# alterable.net
KiCad netlist of a schematic drawn in Altium Designer
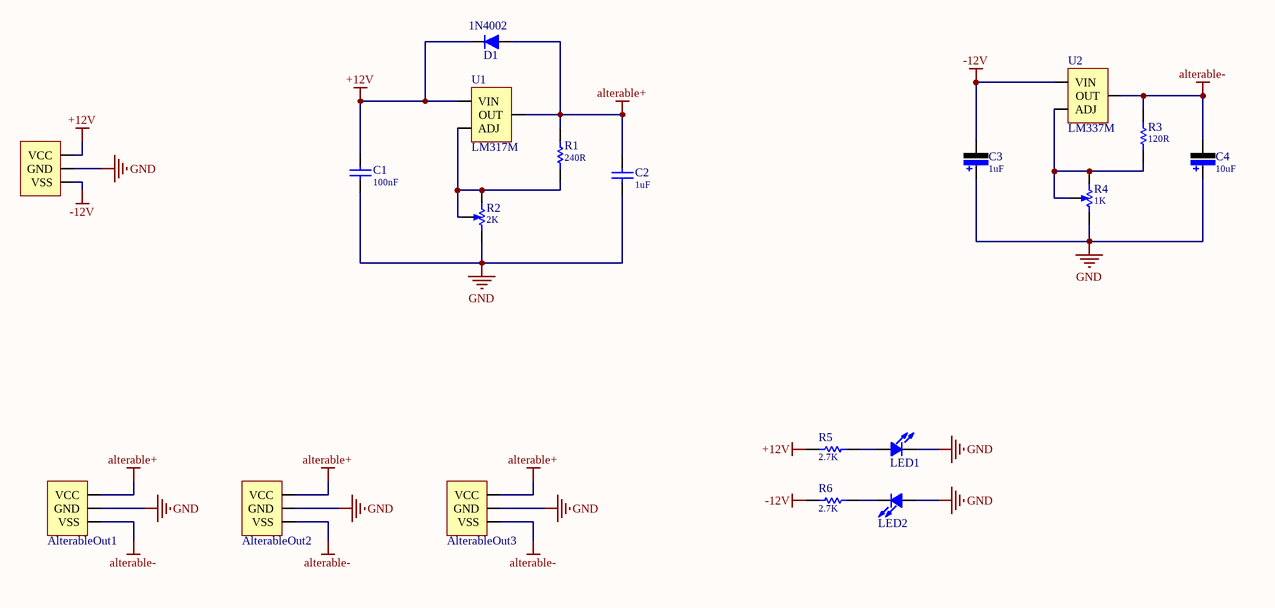
[diagram p0: alterable.SchDoc]

(export (version "E")
  (design (tool "Eeschema 10.0.6"))
  (components
    (comp (ref "AlterableOut1")
      (value "Power-3P")
      (footprint "SIPA03")
      (description "供电端子")
      (libsource (lib "XuZhe") (part "Power-3P"))
    )
    (comp (ref "AlterableOut2")
      (value "Power-3P")
      (footprint "SIPA03")
      (description "供电端子")
      (libsource (lib "XuZhe") (part "Power-3P"))
    )
    (comp (ref "AlterableOut3")
      (value "Power-3P")
      (footprint "SIPA03")
      (description "供电端子")
      (libsource (lib "XuZhe") (part "Power-3P"))
    )
    (comp (ref "C1")
      (value "100nF")
      (footprint "C0603-L")
      (description "贴片瓷片电容")
      (fields (field (name "Comment") "Cap-S"))
      (libsource (lib "XuZhe") (part "Cap-S"))
    )
    (comp (ref "C2")
      (value "1uF")
      (footprint "C0603-L")
      (description "贴片瓷片电容")
      (fields (field (name "Comment") "Cap-S"))
      (libsource (lib "XuZhe") (part "Cap-S"))
    )
    (comp (ref "C3")
      (value "1uF")
      (footprint "C-RB-SD4")
      (description "极性贴片电解电容")
      (fields (field (name "Comment") "C"))
      (libsource (lib "XuZhe") (part "Cap-Pol-ES"))
    )
    (comp (ref "C4")
      (value "10uF")
      (footprint "C-RB-SD4")
      (description "极性贴片电解电容")
      (fields (field (name "Comment") "C"))
      (libsource (lib "XuZhe") (part "Cap-Pol-ES"))
    )
    (comp (ref "D1")
      (value "1N4002")
      (footprint "D-LL34")
      (description "二极管")
      (libsource (lib "XuZhe") (part "Diode"))
    )
    (comp (ref "IN")
      (value "Power-3P")
      (footprint "SIPA03")
      (description "供电端子")
      (libsource (lib "XuZhe") (part "Power-3P"))
    )
    (comp (ref "LED1")
      (value "LED")
      (footprint "Led-0805_L")
      (description "发光二极管")
      (libsource (lib "XuZhe") (part "LED"))
    )
    (comp (ref "LED2")
      (value "LED")
      (footprint "Led-0805_L")
      (description "发光二极管")
      (libsource (lib "XuZhe") (part "LED"))
    )
    (comp (ref "R1")
      (value "240R")
      (footprint "R0603-L")
      (description "贴片电阻")
      (fields (field (name "Comment") "R"))
      (libsource (lib "XuZhe") (part "Res"))
    )
    (comp (ref "R2")
      (value "2K")
      (footprint "R_VR-3296W")
      (description "可调电阻")
      (fields (field (name "Comment") "R"))
      (libsource (lib "XuZhe") (part "Res_Val"))
    )
    (comp (ref "R3")
      (value "120R")
      (footprint "R0603-L")
      (description "贴片电阻")
      (fields (field (name "Comment") "R"))
      (libsource (lib "XuZhe") (part "Res"))
    )
    (comp (ref "R4")
      (value "1K")
      (footprint "R_VR-3296W")
      (description "可调电阻")
      (fields (field (name "Comment") "R"))
      (libsource (lib "XuZhe") (part "Res_Val"))
    )
    (comp (ref "R5")
      (value "2.7K")
      (footprint "R0603-L")
      (description "贴片电阻")
      (fields (field (name "Comment") "R"))
      (libsource (lib "XuZhe") (part "Res"))
    )
    (comp (ref "R6")
      (value "2.7K")
      (footprint "R0603-L")
      (description "贴片电阻")
      (fields (field (name "Comment") "R"))
      (libsource (lib "XuZhe") (part "Res"))
    )
    (comp (ref "U1") (value "LM317M") (footprint "TO-252") (libsource (lib "XuZhe") (part "LM317M")))
    (comp (ref "U2") (value "LM337M") (footprint "TO-252") (libsource (lib "XuZhe") (part "LM337M")))
  )
  (nets
    (net (code "1") (name "+12V") (class "Default")
      (node (ref "C1") (pin "2") (pinfunction "2_2") (pintype "passive"))
      (node (ref "D1") (pin "2") (pinfunction "2_2") (pintype "passive"))
      (node (ref "IN") (pin "1") (pinfunction "VCC_1") (pintype "passive"))
      (node (ref "R5") (pin "1") (pinfunction "1_1") (pintype "passive"))
      (node (ref "U1") (pin "3") (pinfunction "VIN_3") (pintype "passive"))
    )
    (net (code "2") (name "-12V") (class "Default")
      (node (ref "C3") (pin "2") (pinfunction "2_2") (pintype "passive"))
      (node (ref "IN") (pin "3") (pinfunction "VSS_3") (pintype "passive"))
      (node (ref "R6") (pin "1") (pinfunction "1_1") (pintype "passive"))
      (node (ref "U2") (pin "2") (pinfunction "VIN_2") (pintype "passive"))
    )
    (net (code "3") (name "GND") (class "Default")
      (node (ref "AlterableOut1") (pin "2") (pinfunction "GND_2") (pintype "passive"))
      (node (ref "AlterableOut2") (pin "2") (pinfunction "GND_2") (pintype "passive"))
      (node (ref "AlterableOut3") (pin "2") (pinfunction "GND_2") (pintype "passive"))
      (node (ref "C1") (pin "1") (pinfunction "1_1") (pintype "passive"))
      (node (ref "C2") (pin "1") (pinfunction "1_1") (pintype "passive"))
      (node (ref "C3") (pin "1") (pinfunction "1_1") (pintype "passive"))
      (node (ref "C4") (pin "1") (pinfunction "1_1") (pintype "passive"))
      (node (ref "IN") (pin "2") (pinfunction "GND_2") (pintype "passive"))
      (node (ref "LED1") (pin "2") (pinfunction "2_2") (pintype "passive"))
      (node (ref "LED2") (pin "1") (pinfunction "1_1") (pintype "passive"))
      (node (ref "R2") (pin "1") (pinfunction "1_1") (pintype "passive"))
      (node (ref "R4") (pin "1") (pinfunction "1_1") (pintype "passive"))
    )
    (net (code "4") (name "Net-(LED1-Pad1)") (class "Default")
      (node (ref "LED1") (pin "1") (pinfunction "1_1") (pintype "passive"))
      (node (ref "R5") (pin "2") (pinfunction "2_2") (pintype "passive"))
    )
    (net (code "5") (name "Net-(LED2-Pad2)") (class "Default")
      (node (ref "LED2") (pin "2") (pinfunction "2_2") (pintype "passive"))
      (node (ref "R6") (pin "2") (pinfunction "2_2") (pintype "passive"))
    )
    (net (code "6") (name "Net-(U1-ADJ)") (class "Default")
      (node (ref "R1") (pin "1") (pinfunction "1_1") (pintype "passive"))
      (node (ref "R2") (pin "2") (pinfunction "2_2") (pintype "passive"))
      (node (ref "R2") (pin "3") (pinfunction "3_3") (pintype "passive"))
      (node (ref "U1") (pin "1") (pinfunction "ADJ_1") (pintype "passive"))
    )
    (net (code "7") (name "Net-(U2-ADJ)") (class "Default")
      (node (ref "R3") (pin "1") (pinfunction "1_1") (pintype "passive"))
      (node (ref "R4") (pin "2") (pinfunction "2_2") (pintype "passive"))
      (node (ref "R4") (pin "3") (pinfunction "3_3") (pintype "passive"))
      (node (ref "U2") (pin "1") (pinfunction "ADJ_1") (pintype "passive"))
    )
    (net (code "8") (name "alterable+") (class "Default")
      (node (ref "AlterableOut1") (pin "1") (pinfunction "VCC_1") (pintype "passive"))
      (node (ref "AlterableOut2") (pin "1") (pinfunction "VCC_1") (pintype "passive"))
      (node (ref "AlterableOut3") (pin "1") (pinfunction "VCC_1") (pintype "passive"))
      (node (ref "C2") (pin "2") (pinfunction "2_2") (pintype "passive"))
      (node (ref "D1") (pin "1") (pinfunction "1_1") (pintype "passive"))
      (node (ref "R1") (pin "2") (pinfunction "2_2") (pintype "passive"))
      (node (ref "U1") (pin "2") (pinfunction "OUT_2") (pintype "passive"))
    )
    (net (code "9") (name "alterable-") (class "Default")
      (node (ref "AlterableOut1") (pin "3") (pinfunction "VSS_3") (pintype "passive"))
      (node (ref "AlterableOut2") (pin "3") (pinfunction "VSS_3") (pintype "passive"))
      (node (ref "AlterableOut3") (pin "3") (pinfunction "VSS_3") (pintype "passive"))
      (node (ref "C4") (pin "2") (pinfunction "2_2") (pintype "passive"))
      (node (ref "R3") (pin "2") (pinfunction "2_2") (pintype "passive"))
      (node (ref "U2") (pin "3") (pinfunction "OUT_3") (pintype "passive"))
    )
  )
)
